# BatMeas5_2_JST.net
KiCad netlist of a schematic drawn in EAGLE
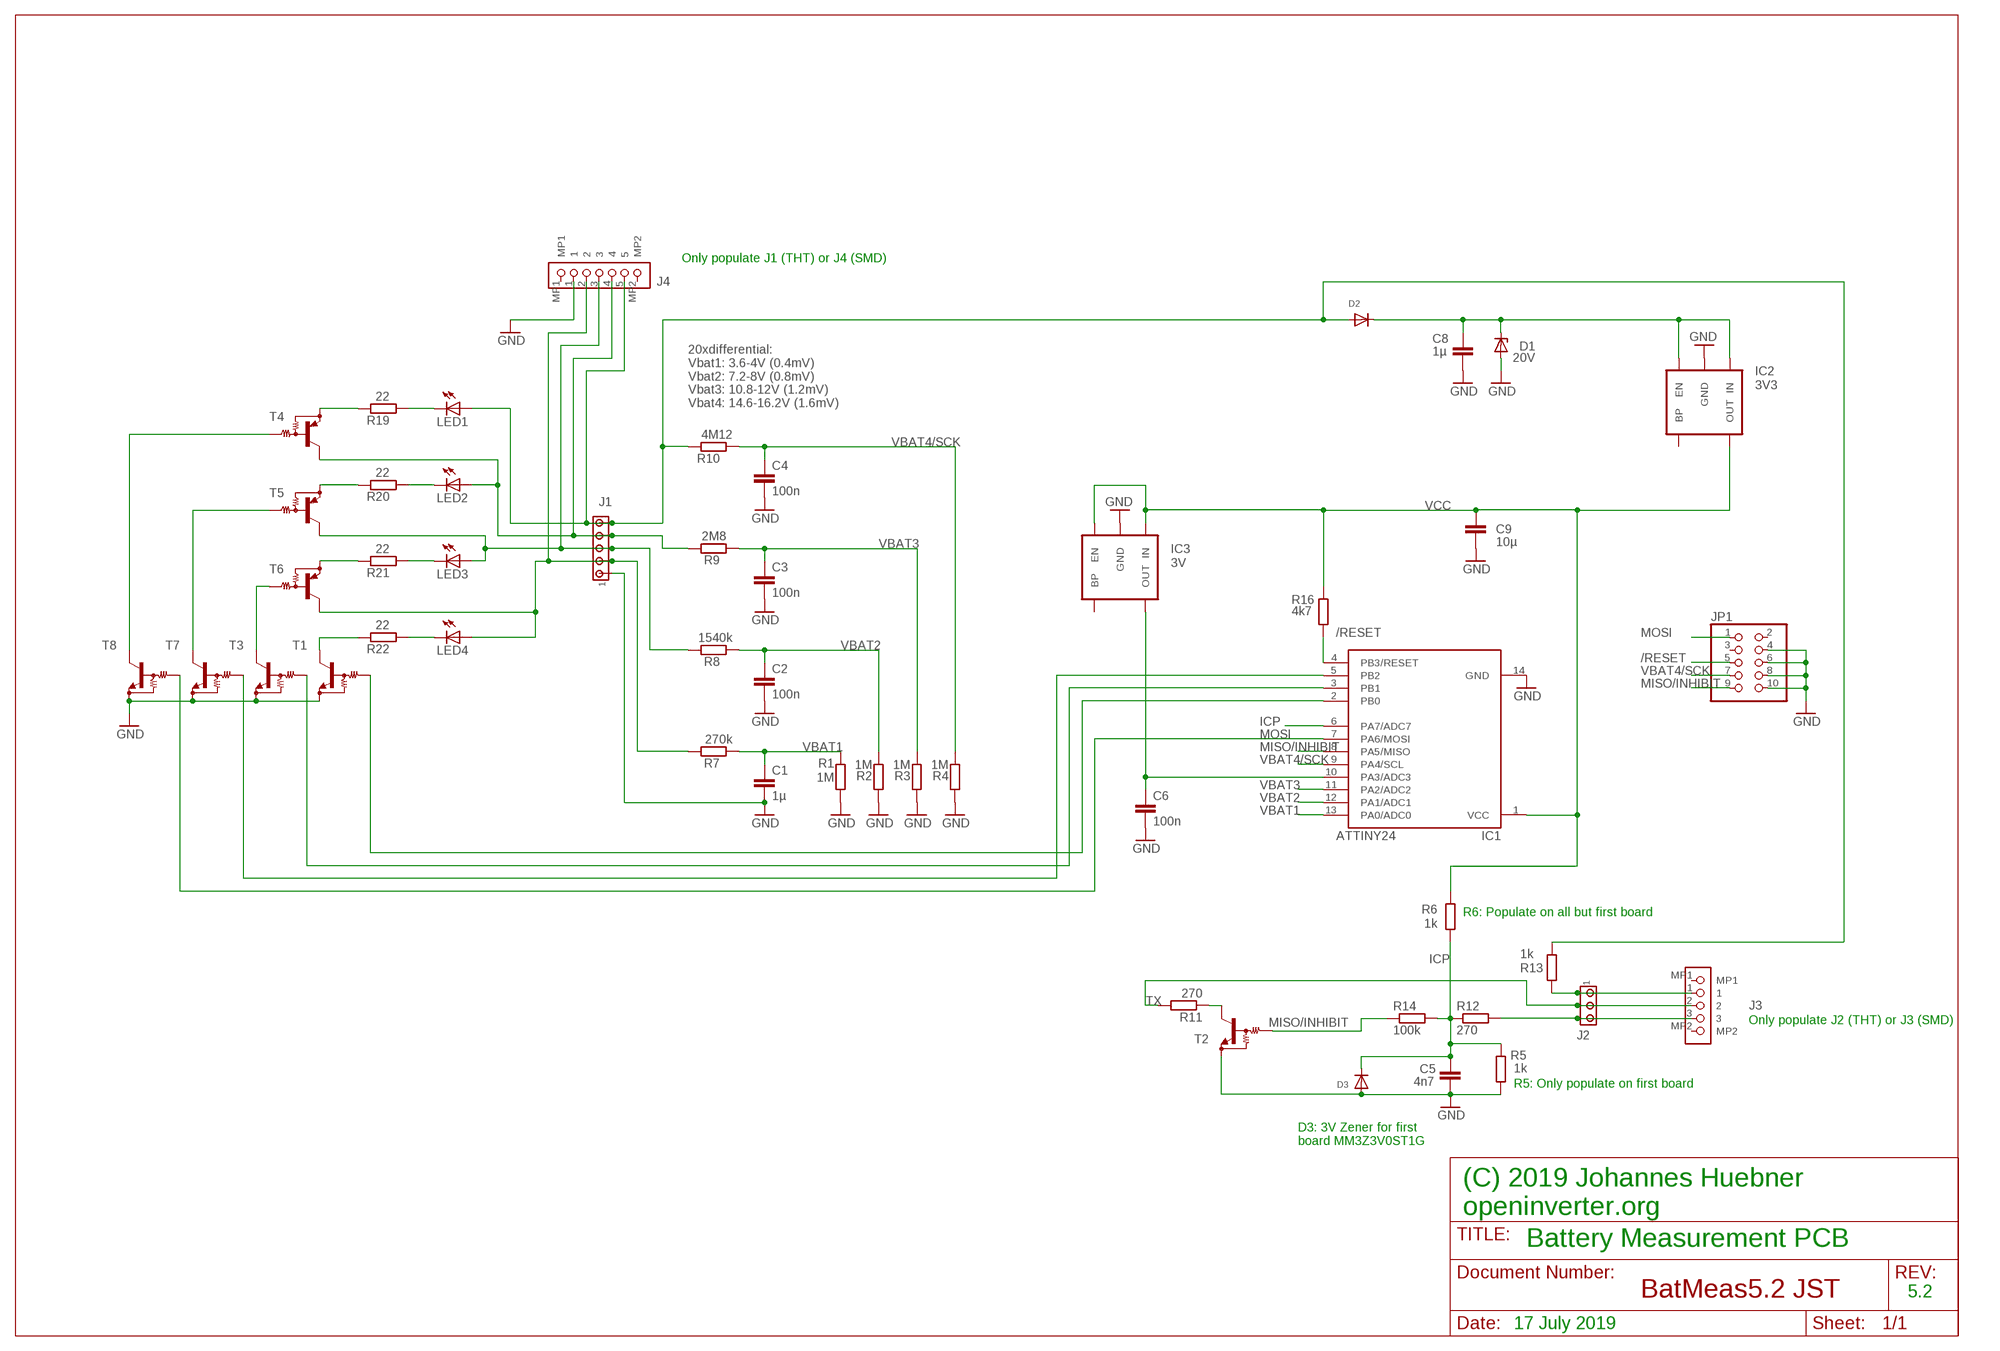
[diagram p0: schematic, sheet 1]

(export (version "E")
  (design (tool "Eeschema 10.0.6"))
  (components
    (comp (ref "C1")
      (value "1µ")
      (footprint "eagle-import:C0603")
      (libsource (lib "eagle-import") (part "C-EUC0603"))
    )
    (comp (ref "C2")
      (value "100n")
      (footprint "eagle-import:C0603")
      (libsource (lib "eagle-import") (part "C-EUC0603"))
    )
    (comp (ref "C3")
      (value "100n")
      (footprint "eagle-import:C0603")
      (libsource (lib "eagle-import") (part "C-EUC0603"))
    )
    (comp (ref "C4")
      (value "100n")
      (footprint "eagle-import:C0603")
      (libsource (lib "eagle-import") (part "C-EUC0603"))
    )
    (comp (ref "C5")
      (value "4n7")
      (footprint "eagle-import:C0603")
      (libsource (lib "eagle-import") (part "C-EUC0603"))
    )
    (comp (ref "C6")
      (value "100n")
      (footprint "eagle-import:C0603")
      (libsource (lib "eagle-import") (part "C-EUC0603"))
    )
    (comp (ref "C8")
      (value "1µ")
      (footprint "eagle-import:C0805")
      (libsource (lib "eagle-import") (part "C-EUC0805"))
    )
    (comp (ref "C9")
      (value "10µ")
      (footprint "eagle-import:C0805")
      (libsource (lib "eagle-import") (part "C-EUC0805"))
    )
    (comp (ref "D1")
      (value "20V")
      (footprint "eagle-import:SMB")
      (libsource (lib "eagle-import") (part "ZENER-DIODESMB"))
    )
    (comp (ref "D2")
      (value "DIODESOD-323F")
      (footprint "eagle-import:SOD-323F")
      (libsource (lib "eagle-import") (part "DIODESOD-323F"))
    )
    (comp (ref "D3")
      (value "DIODESOD-323F")
      (footprint "eagle-import:SOD-323F")
      (libsource (lib "eagle-import") (part "DIODESOD-323F"))
    )
    (comp (ref "IC1")
      (value "ATTINY24")
      (footprint "eagle-import:SO014")
      (libsource (lib "eagle-import") (part "ATTINY24"))
    )
    (comp (ref "IC2")
      (value "3V3")
      (footprint "eagle-import:SOT23-5")
      (libsource (lib "eagle-import") (part "V_REG_LDOSMD"))
    )
    (comp (ref "IC3")
      (value "3V")
      (footprint "eagle-import:SOT23-5")
      (libsource (lib "eagle-import") (part "V_REG_LDOSMD"))
    )
    (comp (ref "J1")
      (value "MTA05-100")
      (footprint "eagle-import:10X05MTA")
      (libsource (lib "eagle-import") (part "MTA05-100"))
    )
    (comp (ref "J2")
      (value "MTA03-100")
      (footprint "eagle-import:10X03MTA")
      (libsource (lib "eagle-import") (part "MTA03-100"))
    )
    (comp (ref "J3")
      (value "BM03B-PASS-1-TFT_(LF)(SN)")
      (footprint "eagle-import:BM03BPASS1TFTLFSN")
      (fields (field (name "MANUFACTURER_PART_NUMBER") "BM03B-PASS-1-TFT (LF)(SN)"))
      (libsource (lib "eagle-import") (part "BM03B-PASS-1-TFT_(LF)(SN)"))
    )
    (comp (ref "J4")
      (value "BM05B-PASS-1-TFT_(LF)(SN)SMD")
      (footprint "eagle-import:BM05BPASS1TFTLFSN")
      (libsource (lib "eagle-import") (part "BM05B-PASS-1-TFT_(LF)(SN)SMD"))
    )
    (comp (ref "JP1")
      (value "PINHD-2X5")
      (footprint "eagle-import:2X05")
      (libsource (lib "eagle-import") (part "PINHD-2X5"))
    )
    (comp (ref "LED1")
      (value "150060GS75000")
      (footprint "eagle-import:CHIPLED_0805")
      (libsource (lib "eagle-import") (part "LEDCHIPLED_0805"))
    )
    (comp (ref "LED2")
      (value "150060GS75000")
      (footprint "eagle-import:CHIPLED_0805")
      (libsource (lib "eagle-import") (part "LEDCHIPLED_0805"))
    )
    (comp (ref "LED3")
      (value "150060GS75000")
      (footprint "eagle-import:CHIPLED_0805")
      (libsource (lib "eagle-import") (part "LEDCHIPLED_0805"))
    )
    (comp (ref "LED4")
      (value "150060GS75000")
      (footprint "eagle-import:CHIPLED_0805")
      (libsource (lib "eagle-import") (part "LEDCHIPLED_0805"))
    )
    (comp (ref "R1")
      (value "1M")
      (footprint "eagle-import:R0603")
      (libsource (lib "eagle-import") (part "R-EU_R0603"))
    )
    (comp (ref "R2")
      (value "1M")
      (footprint "eagle-import:R0603")
      (libsource (lib "eagle-import") (part "R-EU_R0603"))
    )
    (comp (ref "R3")
      (value "1M")
      (footprint "eagle-import:R0603")
      (libsource (lib "eagle-import") (part "R-EU_R0603"))
    )
    (comp (ref "R4")
      (value "1M")
      (footprint "eagle-import:R0603")
      (libsource (lib "eagle-import") (part "R-EU_R0603"))
    )
    (comp (ref "R5")
      (value "1k")
      (footprint "eagle-import:R0603")
      (libsource (lib "eagle-import") (part "R-EU_R0603"))
    )
    (comp (ref "R6")
      (value "1k")
      (footprint "eagle-import:R0603")
      (libsource (lib "eagle-import") (part "R-EU_R0603"))
    )
    (comp (ref "R7")
      (value "270k")
      (footprint "eagle-import:R0603")
      (libsource (lib "eagle-import") (part "R-EU_R0603"))
    )
    (comp (ref "R8")
      (value "1540k")
      (footprint "eagle-import:R0603")
      (libsource (lib "eagle-import") (part "R-EU_R0603"))
    )
    (comp (ref "R9")
      (value "2M8")
      (footprint "eagle-import:R0603")
      (libsource (lib "eagle-import") (part "R-EU_R0603"))
    )
    (comp (ref "R10")
      (value "4M12")
      (footprint "eagle-import:R0603")
      (libsource (lib "eagle-import") (part "R-EU_R0603"))
    )
    (comp (ref "R11")
      (value "270")
      (footprint "eagle-import:R0603")
      (libsource (lib "eagle-import") (part "R-EU_R0603"))
    )
    (comp (ref "R12")
      (value "270")
      (footprint "eagle-import:R0603")
      (libsource (lib "eagle-import") (part "R-EU_R0603"))
    )
    (comp (ref "R13")
      (value "1k")
      (footprint "eagle-import:R0603")
      (libsource (lib "eagle-import") (part "R-EU_R0603"))
    )
    (comp (ref "R14")
      (value "100k")
      (footprint "eagle-import:R0603")
      (libsource (lib "eagle-import") (part "R-EU_R0603"))
    )
    (comp (ref "R16")
      (value "4k7")
      (footprint "eagle-import:R0603")
      (libsource (lib "eagle-import") (part "R-EU_R0603"))
    )
    (comp (ref "R19")
      (value "22")
      (footprint "eagle-import:R0805")
      (libsource (lib "eagle-import") (part "R-EU_R0805"))
    )
    (comp (ref "R20")
      (value "22")
      (footprint "eagle-import:R0805")
      (libsource (lib "eagle-import") (part "R-EU_R0805"))
    )
    (comp (ref "R21")
      (value "22")
      (footprint "eagle-import:R0805")
      (libsource (lib "eagle-import") (part "R-EU_R0805"))
    )
    (comp (ref "R22")
      (value "22")
      (footprint "eagle-import:R0805")
      (libsource (lib "eagle-import") (part "R-EU_R0805"))
    )
    (comp (ref "T1")
      (value "MMUN2233")
      (footprint "eagle-import:SC59-BEC")
      (libsource (lib "eagle-import") (part "-NPN_DRIVER-SC59-BECMUN2211T1"))
    )
    (comp (ref "T2")
      (value "MMUN2233")
      (footprint "eagle-import:SC59-BEC")
      (libsource (lib "eagle-import") (part "-NPN_DRIVER-SC59-BECMUN2211T1"))
    )
    (comp (ref "T3")
      (value "MMUN2233")
      (footprint "eagle-import:SC59-BEC")
      (libsource (lib "eagle-import") (part "-NPN_DRIVER-SC59-BECMUN2211T1"))
    )
    (comp (ref "T4")
      (value "MMUN2111LT1G")
      (footprint "eagle-import:SC59-BEC")
      (libsource (lib "eagle-import") (part "-PNP_DRIVER-SC59-BECMUN2111T1"))
    )
    (comp (ref "T5")
      (value "MMUN2111LT1G")
      (footprint "eagle-import:SC59-BEC")
      (libsource (lib "eagle-import") (part "-PNP_DRIVER-SC59-BECMUN2111T1"))
    )
    (comp (ref "T6")
      (value "MMUN2111LT1G")
      (footprint "eagle-import:SC59-BEC")
      (libsource (lib "eagle-import") (part "-PNP_DRIVER-SC59-BECMUN2111T1"))
    )
    (comp (ref "T7")
      (value "MMUN2233")
      (footprint "eagle-import:SC59-BEC")
      (libsource (lib "eagle-import") (part "-NPN_DRIVER-SC59-BECMUN2211T1"))
    )
    (comp (ref "T8")
      (value "MMUN2233")
      (footprint "eagle-import:SC59-BEC")
      (libsource (lib "eagle-import") (part "-NPN_DRIVER-SC59-BECMUN2211T1"))
    )
  )
  (nets
    (net (code "1") (name "/ICP") (class "Default")
      (node (ref "C5") (pin "1") (pinfunction "1_1") (pintype "passive"))
      (node (ref "D3") (pin "C") (pinfunction "C_C") (pintype "passive"))
      (node (ref "IC1") (pin "6") (pinfunction "PA7/ADC7_6") (pintype "bidirectional"))
      (node (ref "R12") (pin "1") (pinfunction "1_1") (pintype "passive"))
      (node (ref "R14") (pin "2") (pinfunction "2_2") (pintype "passive"))
      (node (ref "R5") (pin "2") (pinfunction "2_2") (pintype "passive"))
      (node (ref "R6") (pin "1") (pinfunction "1_1") (pintype "passive"))
    )
    (net (code "2") (name "/MISO{slash}INHIBIT") (class "Default")
      (node (ref "IC1") (pin "8") (pinfunction "PA5/MISO_8") (pintype "bidirectional"))
      (node (ref "JP1") (pin "9") (pinfunction "9_9") (pintype "passive"))
      (node (ref "R14") (pin "1") (pinfunction "1_1") (pintype "passive"))
      (node (ref "T2") (pin "B") (pinfunction "B_B") (pintype "passive"))
    )
    (net (code "3") (name "/MOSI") (class "Default")
      (node (ref "IC1") (pin "7") (pinfunction "PA6/MOSI_7") (pintype "bidirectional"))
      (node (ref "JP1") (pin "1") (pinfunction "1_1") (pintype "passive"))
      (node (ref "T8") (pin "B") (pinfunction "B_B") (pintype "passive"))
    )
    (net (code "4") (name "/TX") (class "Default")
      (node (ref "J2") (pin "2") (pinfunction "2_2") (pintype "passive"))
      (node (ref "J3") (pin "2") (pinfunction "2_2") (pintype "bidirectional"))
      (node (ref "R11") (pin "2") (pinfunction "2_2") (pintype "passive"))
    )
    (net (code "5") (name "/VBAT1") (class "Default")
      (node (ref "C1") (pin "1") (pinfunction "1_1") (pintype "passive"))
      (node (ref "IC1") (pin "13") (pinfunction "PA0/ADC0_13") (pintype "bidirectional"))
      (node (ref "R1") (pin "1") (pinfunction "1_1") (pintype "passive"))
      (node (ref "R7") (pin "1") (pinfunction "1_1") (pintype "passive"))
    )
    (net (code "6") (name "/VBAT2") (class "Default")
      (node (ref "C2") (pin "1") (pinfunction "1_1") (pintype "passive"))
      (node (ref "IC1") (pin "12") (pinfunction "PA1/ADC1_12") (pintype "bidirectional"))
      (node (ref "R2") (pin "1") (pinfunction "1_1") (pintype "passive"))
      (node (ref "R8") (pin "1") (pinfunction "1_1") (pintype "passive"))
    )
    (net (code "7") (name "/VBAT3") (class "Default")
      (node (ref "C3") (pin "1") (pinfunction "1_1") (pintype "passive"))
      (node (ref "IC1") (pin "11") (pinfunction "PA2/ADC2_11") (pintype "bidirectional"))
      (node (ref "R3") (pin "1") (pinfunction "1_1") (pintype "passive"))
      (node (ref "R9") (pin "1") (pinfunction "1_1") (pintype "passive"))
    )
    (net (code "8") (name "/VBAT4{slash}SCK") (class "Default")
      (node (ref "C4") (pin "1") (pinfunction "1_1") (pintype "passive"))
      (node (ref "IC1") (pin "9") (pinfunction "PA4/SCL_9") (pintype "bidirectional"))
      (node (ref "JP1") (pin "7") (pinfunction "7_7") (pintype "passive"))
      (node (ref "R10") (pin "1") (pinfunction "1_1") (pintype "passive"))
      (node (ref "R4") (pin "1") (pinfunction "1_1") (pintype "passive"))
    )
    (net (code "9") (name "/VCC") (class "Default")
      (node (ref "C9") (pin "1") (pinfunction "1_1") (pintype "passive"))
      (node (ref "IC1") (pin "1") (pinfunction "VCC_1") (pintype "bidirectional"))
      (node (ref "IC2") (pin "5") (pinfunction "OUT_5") (pintype "passive"))
      (node (ref "IC3") (pin "1") (pinfunction "IN_1") (pintype "input"))
      (node (ref "IC3") (pin "3") (pinfunction "EN_3") (pintype "input"))
      (node (ref "R16") (pin "1") (pinfunction "1_1") (pintype "passive"))
      (node (ref "R6") (pin "2") (pinfunction "2_2") (pintype "passive"))
    )
    (net (code "10") (name "/{slash}RESET") (class "Default")
      (node (ref "IC1") (pin "4") (pinfunction "PB3/RESET_4") (pintype "bidirectional"))
      (node (ref "JP1") (pin "5") (pinfunction "5_5") (pintype "passive"))
      (node (ref "R16") (pin "2") (pinfunction "2_2") (pintype "passive"))
    )
    (net (code "11") (name "GND") (class "Default")
      (node (ref "C1") (pin "2") (pinfunction "2_2") (pintype "passive"))
      (node (ref "C2") (pin "2") (pinfunction "2_2") (pintype "passive"))
      (node (ref "C3") (pin "2") (pinfunction "2_2") (pintype "passive"))
      (node (ref "C4") (pin "2") (pinfunction "2_2") (pintype "passive"))
      (node (ref "C5") (pin "2") (pinfunction "2_2") (pintype "passive"))
      (node (ref "C6") (pin "2") (pinfunction "2_2") (pintype "passive"))
      (node (ref "C8") (pin "2") (pinfunction "2_2") (pintype "passive"))
      (node (ref "C9") (pin "2") (pinfunction "2_2") (pintype "passive"))
      (node (ref "D1") (pin "A") (pinfunction "A_A") (pintype "passive"))
      (node (ref "D3") (pin "A") (pinfunction "A_A") (pintype "passive"))
      (node (ref "IC1") (pin "14") (pinfunction "GND_14") (pintype "bidirectional"))
      (node (ref "IC2") (pin "2") (pinfunction "GND_2") (pintype "input"))
      (node (ref "IC3") (pin "2") (pinfunction "GND_2") (pintype "input"))
      (node (ref "J1") (pin "1") (pinfunction "1_1") (pintype "passive"))
      (node (ref "J4") (pin "1") (pinfunction "1_1") (pintype "bidirectional"))
      (node (ref "JP1") (pin "10") (pinfunction "10_10") (pintype "passive"))
      (node (ref "JP1") (pin "4") (pinfunction "4_4") (pintype "passive"))
      (node (ref "JP1") (pin "6") (pinfunction "6_6") (pintype "passive"))
      (node (ref "JP1") (pin "8") (pinfunction "8_8") (pintype "passive"))
      (node (ref "R1") (pin "2") (pinfunction "2_2") (pintype "passive"))
      (node (ref "R2") (pin "2") (pinfunction "2_2") (pintype "passive"))
      (node (ref "R3") (pin "2") (pinfunction "2_2") (pintype "passive"))
      (node (ref "R4") (pin "2") (pinfunction "2_2") (pintype "passive"))
      (node (ref "R5") (pin "1") (pinfunction "1_1") (pintype "passive"))
      (node (ref "T1") (pin "E") (pinfunction "E_E") (pintype "passive"))
      (node (ref "T2") (pin "E") (pinfunction "E_E") (pintype "passive"))
      (node (ref "T3") (pin "E") (pinfunction "E_E") (pintype "passive"))
      (node (ref "T7") (pin "E") (pinfunction "E_E") (pintype "passive"))
      (node (ref "T8") (pin "E") (pinfunction "E_E") (pintype "passive"))
    )
    (net (code "12") (name "Net-(D2-PadA)") (class "Default")
      (node (ref "D2") (pin "A") (pinfunction "A_A") (pintype "passive"))
      (node (ref "J1") (pin "5") (pinfunction "5_5") (pintype "passive"))
      (node (ref "J4") (pin "5") (pinfunction "5_5") (pintype "bidirectional"))
      (node (ref "LED1") (pin "A") (pinfunction "A_A") (pintype "passive"))
      (node (ref "R10") (pin "2") (pinfunction "2_2") (pintype "passive"))
      (node (ref "R13") (pin "1") (pinfunction "1_1") (pintype "passive"))
    )
    (net (code "13") (name "Net-(IC1-PA3{slash}ADC3)") (class "Default")
      (node (ref "C6") (pin "1") (pinfunction "1_1") (pintype "passive"))
      (node (ref "IC1") (pin "10") (pinfunction "PA3/ADC3_10") (pintype "bidirectional"))
      (node (ref "IC3") (pin "5") (pinfunction "OUT_5") (pintype "passive"))
    )
    (net (code "14") (name "Net-(IC1-PB0)") (class "Default")
      (node (ref "IC1") (pin "2") (pinfunction "PB0_2") (pintype "bidirectional"))
      (node (ref "T1") (pin "B") (pinfunction "B_B") (pintype "passive"))
    )
    (net (code "15") (name "Net-(IC1-PB1)") (class "Default")
      (node (ref "IC1") (pin "3") (pinfunction "PB1_3") (pintype "bidirectional"))
      (node (ref "T3") (pin "B") (pinfunction "B_B") (pintype "passive"))
    )
    (net (code "16") (name "Net-(IC1-PB2)") (class "Default")
      (node (ref "IC1") (pin "5") (pinfunction "PB2_5") (pintype "bidirectional"))
      (node (ref "T7") (pin "B") (pinfunction "B_B") (pintype "passive"))
    )
    (net (code "17") (name "Net-(IC2-EN)") (class "Default")
      (node (ref "C8") (pin "1") (pinfunction "1_1") (pintype "passive"))
      (node (ref "D1") (pin "C") (pinfunction "C_C") (pintype "passive"))
      (node (ref "D2") (pin "C") (pinfunction "C_C") (pintype "passive"))
      (node (ref "IC2") (pin "1") (pinfunction "IN_1") (pintype "input"))
      (node (ref "IC2") (pin "3") (pinfunction "EN_3") (pintype "input"))
    )
    (net (code "18") (name "Net-(J1-Pad2)") (class "Default")
      (node (ref "J1") (pin "2") (pinfunction "2_2") (pintype "passive"))
      (node (ref "J4") (pin "2") (pinfunction "2_2") (pintype "bidirectional"))
      (node (ref "LED4") (pin "A") (pinfunction "A_A") (pintype "passive"))
      (node (ref "R7") (pin "2") (pinfunction "2_2") (pintype "passive"))
      (node (ref "T6") (pin "C") (pinfunction "C_C") (pintype "passive"))
    )
    (net (code "19") (name "Net-(J1-Pad3)") (class "Default")
      (node (ref "J1") (pin "3") (pinfunction "3_3") (pintype "passive"))
      (node (ref "J4") (pin "3") (pinfunction "3_3") (pintype "bidirectional"))
      (node (ref "LED3") (pin "A") (pinfunction "A_A") (pintype "passive"))
      (node (ref "R8") (pin "2") (pinfunction "2_2") (pintype "passive"))
      (node (ref "T5") (pin "C") (pinfunction "C_C") (pintype "passive"))
    )
    (net (code "20") (name "Net-(J1-Pad4)") (class "Default")
      (node (ref "J1") (pin "4") (pinfunction "4_4") (pintype "passive"))
      (node (ref "J4") (pin "4") (pinfunction "4_4") (pintype "bidirectional"))
      (node (ref "LED2") (pin "A") (pinfunction "A_A") (pintype "passive"))
      (node (ref "R9") (pin "2") (pinfunction "2_2") (pintype "passive"))
      (node (ref "T4") (pin "C") (pinfunction "C_C") (pintype "passive"))
    )
    (net (code "21") (name "Net-(J2-Pad1)") (class "Default")
      (node (ref "J2") (pin "1") (pinfunction "1_1") (pintype "passive"))
      (node (ref "J3") (pin "1") (pinfunction "1_1") (pintype "bidirectional"))
      (node (ref "R13") (pin "2") (pinfunction "2_2") (pintype "passive"))
    )
    (net (code "22") (name "Net-(J2-Pad3)") (class "Default")
      (node (ref "J2") (pin "3") (pinfunction "3_3") (pintype "passive"))
      (node (ref "J3") (pin "3") (pinfunction "3_3") (pintype "bidirectional"))
      (node (ref "R12") (pin "2") (pinfunction "2_2") (pintype "passive"))
    )
    (net (code "23") (name "Net-(LED1-PadC)") (class "Default")
      (node (ref "LED1") (pin "C") (pinfunction "C_C") (pintype "passive"))
      (node (ref "R19") (pin "1") (pinfunction "1_1") (pintype "passive"))
    )
    (net (code "24") (name "Net-(LED2-PadC)") (class "Default")
      (node (ref "LED2") (pin "C") (pinfunction "C_C") (pintype "passive"))
      (node (ref "R20") (pin "1") (pinfunction "1_1") (pintype "passive"))
    )
    (net (code "25") (name "Net-(LED3-PadC)") (class "Default")
      (node (ref "LED3") (pin "C") (pinfunction "C_C") (pintype "passive"))
      (node (ref "R21") (pin "1") (pinfunction "1_1") (pintype "passive"))
    )
    (net (code "26") (name "Net-(LED4-PadC)") (class "Default")
      (node (ref "LED4") (pin "C") (pinfunction "C_C") (pintype "passive"))
      (node (ref "R22") (pin "1") (pinfunction "1_1") (pintype "passive"))
    )
    (net (code "27") (name "Net-(R11-Pad1)") (class "Default")
      (node (ref "R11") (pin "1") (pinfunction "1_1") (pintype "passive"))
      (node (ref "T2") (pin "C") (pinfunction "C_C") (pintype "passive"))
    )
    (net (code "28") (name "Net-(R19-Pad2)") (class "Default")
      (node (ref "R19") (pin "2") (pinfunction "2_2") (pintype "passive"))
      (node (ref "T4") (pin "E") (pinfunction "E_E") (pintype "passive"))
    )
    (net (code "29") (name "Net-(R20-Pad2)") (class "Default")
      (node (ref "R20") (pin "2") (pinfunction "2_2") (pintype "passive"))
      (node (ref "T5") (pin "E") (pinfunction "E_E") (pintype "passive"))
    )
    (net (code "30") (name "Net-(R21-Pad2)") (class "Default")
      (node (ref "R21") (pin "2") (pinfunction "2_2") (pintype "passive"))
      (node (ref "T6") (pin "E") (pinfunction "E_E") (pintype "passive"))
    )
    (net (code "31") (name "Net-(R22-Pad2)") (class "Default")
      (node (ref "R22") (pin "2") (pinfunction "2_2") (pintype "passive"))
      (node (ref "T1") (pin "C") (pinfunction "C_C") (pintype "passive"))
    )
    (net (code "32") (name "Net-(T3-PadC)") (class "Default")
      (node (ref "T3") (pin "C") (pinfunction "C_C") (pintype "passive"))
      (node (ref "T6") (pin "B") (pinfunction "B_B") (pintype "passive"))
    )
    (net (code "33") (name "Net-(T4-PadB)") (class "Default")
      (node (ref "T4") (pin "B") (pinfunction "B_B") (pintype "passive"))
      (node (ref "T8") (pin "C") (pinfunction "C_C") (pintype "passive"))
    )
    (net (code "34") (name "Net-(T5-PadB)") (class "Default")
      (node (ref "T5") (pin "B") (pinfunction "B_B") (pintype "passive"))
      (node (ref "T7") (pin "C") (pinfunction "C_C") (pintype "passive"))
    )
    (net (code "35") (name "unconnected-(IC2-BP-Pad4)") (class "Default")
      (node (ref "IC2") (pin "4") (pinfunction "BP_4") (pintype "input"))
    )
    (net (code "36") (name "unconnected-(IC3-BP-Pad4)") (class "Default")
      (node (ref "IC3") (pin "4") (pinfunction "BP_4") (pintype "input"))
    )
    (net (code "37") (name "unconnected-(J3-PadMP1)") (class "Default")
      (node (ref "J3") (pin "MP1") (pinfunction "MP1_MP1") (pintype "bidirectional"))
    )
    (net (code "38") (name "unconnected-(J3-PadMP2)") (class "Default")
      (node (ref "J3") (pin "MP2") (pinfunction "MP2_MP2") (pintype "bidirectional"))
    )
    (net (code "39") (name "unconnected-(J4-PadMP1)") (class "Default")
      (node (ref "J4") (pin "MP1") (pinfunction "MP1_MP1") (pintype "bidirectional"))
    )
    (net (code "40") (name "unconnected-(J4-PadMP2)") (class "Default")
      (node (ref "J4") (pin "MP2") (pinfunction "MP2_MP2") (pintype "bidirectional"))
    )
    (net (code "41") (name "unconnected-(JP1-Pad2)") (class "Default")
      (node (ref "JP1") (pin "2") (pinfunction "2_2") (pintype "passive"))
    )
    (net (code "42") (name "unconnected-(JP1-Pad3)") (class "Default")
      (node (ref "JP1") (pin "3") (pinfunction "3_3") (pintype "passive"))
    )
  )
)
